# FPGA_Bypass_3V3.net
KiCad netlist of a schematic drawn in Altium Designer
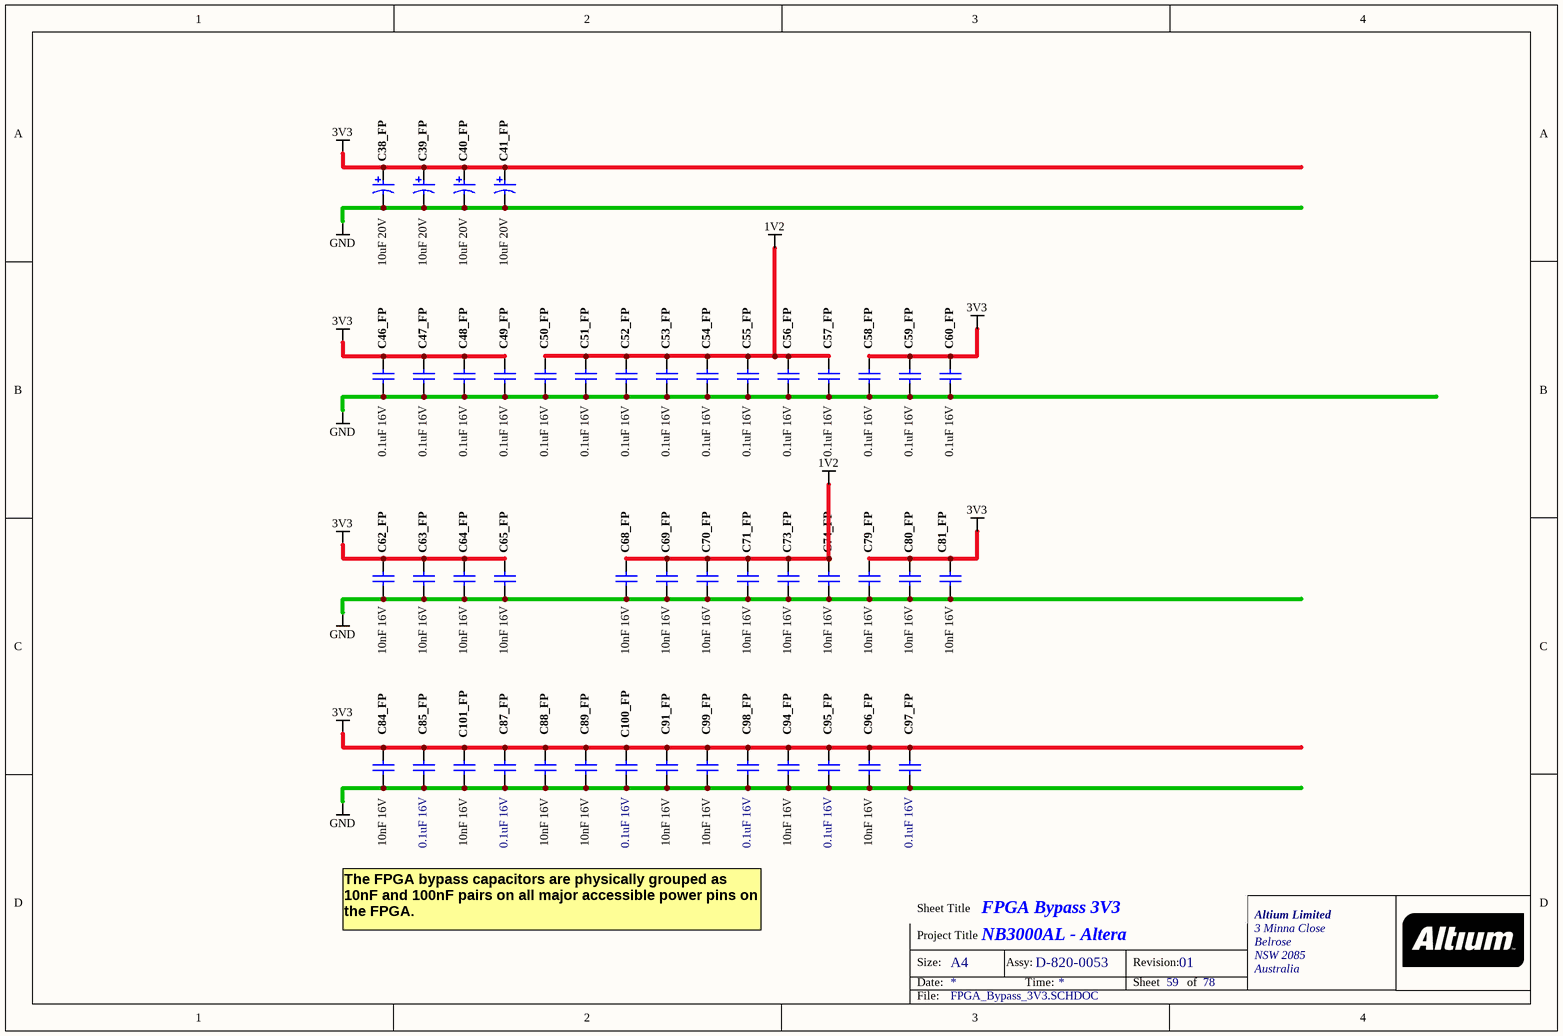
[diagram p0: FPGA_Bypass_3V3.SCHDOC]

(export (version "E")
  (design (tool "Eeschema 10.0.6"))
  (components
    (comp (ref "C38_FP")
      (value "10uF 20V")
      (footprint "CAPC3528-STAR")
      (description "Capacitor, Tantalum, 10uF 10% 20V MCCT-B (3528)")
      (fields (field (name "TOLERANCE") "10 %"))
      (libsource (lib "altium-import") (part "root_0_CAP-P_"))
    )
    (comp (ref "C39_FP")
      (value "10uF 20V")
      (footprint "CAPC3528-STAR")
      (description "Capacitor, Tantalum, 10uF 10% 20V MCCT-B (3528)")
      (fields (field (name "TOLERANCE") "10 %"))
      (libsource (lib "altium-import") (part "root_0_CAP-P_"))
    )
    (comp (ref "C40_FP")
      (value "10uF 20V")
      (footprint "CAPC3528-STAR")
      (description "Capacitor, Tantalum, 10uF 10% 20V MCCT-B (3528)")
      (fields (field (name "TOLERANCE") "10 %"))
      (libsource (lib "altium-import") (part "root_0_CAP-P_"))
    )
    (comp (ref "C41_FP")
      (value "10uF 20V")
      (footprint "CAPC3528-STAR")
      (description "Capacitor, Tantalum, 10uF 10% 20V MCCT-B (3528)")
      (fields (field (name "TOLERANCE") "10 %"))
      (libsource (lib "altium-import") (part "root_0_CAP-P_"))
    )
    (comp (ref "C46_FP")
      (value "0.1uF 16V")
      (footprint "CAPC1005-STAR")
      (description "Capacitor, Ceramic, 0.1uF 10% 16V 0402 (1005) X7R")
      (fields (field (name "TOLERANCE") "10 %"))
      (libsource (lib "altium-import") (part "root_0_mirrored_CAP-NP_"))
    )
    (comp (ref "C47_FP")
      (value "0.1uF 16V")
      (footprint "CAPC1005-STAR")
      (description "Capacitor, Ceramic, 0.1uF 10% 16V 0402 (1005) X7R")
      (fields (field (name "TOLERANCE") "10 %"))
      (libsource (lib "altium-import") (part "root_0_mirrored_CAP-NP_"))
    )
    (comp (ref "C48_FP")
      (value "0.1uF 16V")
      (footprint "CAPC1005-STAR")
      (description "Capacitor, Ceramic, 0.1uF 10% 16V 0402 (1005) X7R")
      (fields (field (name "TOLERANCE") "10 %"))
      (libsource (lib "altium-import") (part "root_0_mirrored_CAP-NP_"))
    )
    (comp (ref "C49_FP")
      (value "0.1uF 16V")
      (footprint "CAPC1005-STAR")
      (description "Capacitor, Ceramic, 0.1uF 10% 16V 0402 (1005) X7R")
      (fields (field (name "TOLERANCE") "10 %"))
      (libsource (lib "altium-import") (part "root_0_mirrored_CAP-NP_"))
    )
    (comp (ref "C50_FP")
      (value "0.1uF 16V")
      (footprint "CAPC1005-STAR")
      (description "Capacitor, Ceramic, 0.1uF 10% 16V 0402 (1005) X7R")
      (fields (field (name "TOLERANCE") "10 %"))
      (libsource (lib "altium-import") (part "root_0_mirrored_CAP-NP_"))
    )
    (comp (ref "C51_FP")
      (value "0.1uF 16V")
      (footprint "CAPC1005-STAR")
      (description "Capacitor, Ceramic, 0.1uF 10% 16V 0402 (1005) X7R")
      (fields (field (name "TOLERANCE") "10 %"))
      (libsource (lib "altium-import") (part "root_0_mirrored_CAP-NP_"))
    )
    (comp (ref "C52_FP")
      (value "0.1uF 16V")
      (footprint "CAPC1005-STAR")
      (description "Capacitor, Ceramic, 0.1uF 10% 16V 0402 (1005) X7R")
      (fields (field (name "TOLERANCE") "10 %"))
      (libsource (lib "altium-import") (part "root_0_mirrored_CAP-NP_"))
    )
    (comp (ref "C53_FP")
      (value "0.1uF 16V")
      (footprint "CAPC1005-STAR")
      (description "Capacitor, Ceramic, 0.1uF 10% 16V 0402 (1005) X7R")
      (fields (field (name "TOLERANCE") "10 %"))
      (libsource (lib "altium-import") (part "root_0_mirrored_CAP-NP_"))
    )
    (comp (ref "C54_FP")
      (value "0.1uF 16V")
      (footprint "CAPC1005-STAR")
      (description "Capacitor, Ceramic, 0.1uF 10% 16V 0402 (1005) X7R")
      (fields (field (name "TOLERANCE") "10 %"))
      (libsource (lib "altium-import") (part "root_0_mirrored_CAP-NP_"))
    )
    (comp (ref "C55_FP")
      (value "0.1uF 16V")
      (footprint "CAPC1005-STAR")
      (description "Capacitor, Ceramic, 0.1uF 10% 16V 0402 (1005) X7R")
      (fields (field (name "TOLERANCE") "10 %"))
      (libsource (lib "altium-import") (part "root_0_mirrored_CAP-NP_"))
    )
    (comp (ref "C56_FP")
      (value "0.1uF 16V")
      (footprint "CAPC1005-STAR")
      (description "Capacitor, Ceramic, 0.1uF 10% 16V 0402 (1005) X7R")
      (fields (field (name "TOLERANCE") "10 %"))
      (libsource (lib "altium-import") (part "root_0_mirrored_CAP-NP_"))
    )
    (comp (ref "C57_FP")
      (value "0.1uF 16V")
      (footprint "CAPC1005-STAR")
      (description "Capacitor, Ceramic, 0.1uF 10% 16V 0402 (1005) X7R")
      (fields (field (name "TOLERANCE") "10 %"))
      (libsource (lib "altium-import") (part "root_0_mirrored_CAP-NP_"))
    )
    (comp (ref "C58_FP")
      (value "0.1uF 16V")
      (footprint "CAPC1005-STAR")
      (description "Capacitor, Ceramic, 0.1uF 10% 16V 0402 (1005) X7R")
      (fields (field (name "TOLERANCE") "10 %"))
      (libsource (lib "altium-import") (part "root_0_mirrored_CAP-NP_"))
    )
    (comp (ref "C59_FP")
      (value "0.1uF 16V")
      (footprint "CAPC1005-STAR")
      (description "Capacitor, Ceramic, 0.1uF 10% 16V 0402 (1005) X7R")
      (fields (field (name "TOLERANCE") "10 %"))
      (libsource (lib "altium-import") (part "root_0_mirrored_CAP-NP_"))
    )
    (comp (ref "C60_FP")
      (value "0.1uF 16V")
      (footprint "CAPC1005-STAR")
      (description "Capacitor, Ceramic, 0.1uF 10% 16V 0402 (1005) X7R")
      (fields (field (name "TOLERANCE") "10 %"))
      (libsource (lib "altium-import") (part "root_0_mirrored_CAP-NP_"))
    )
    (comp (ref "C62_FP")
      (value "10nF 16V")
      (footprint "CAPC1005-STAR")
      (description "Capacitor, Ceramic, 10nF 10% 16V 0402 (1005) X7R")
      (fields (field (name "TOLERANCE") "10 %"))
      (libsource (lib "altium-import") (part "root_0_CAP-NP_"))
    )
    (comp (ref "C63_FP")
      (value "10nF 16V")
      (footprint "CAPC1005-STAR")
      (description "Capacitor, Ceramic, 10nF 10% 16V 0402 (1005) X7R")
      (fields (field (name "TOLERANCE") "10 %"))
      (libsource (lib "altium-import") (part "root_0_CAP-NP_"))
    )
    (comp (ref "C64_FP")
      (value "10nF 16V")
      (footprint "CAPC1005-STAR")
      (description "Capacitor, Ceramic, 10nF 10% 16V 0402 (1005) X7R")
      (fields (field (name "TOLERANCE") "10 %"))
      (libsource (lib "altium-import") (part "root_0_CAP-NP_"))
    )
    (comp (ref "C65_FP")
      (value "10nF 16V")
      (footprint "CAPC1005-STAR")
      (description "Capacitor, Ceramic, 10nF 10% 16V 0402 (1005) X7R")
      (fields (field (name "TOLERANCE") "10 %"))
      (libsource (lib "altium-import") (part "root_0_CAP-NP_"))
    )
    (comp (ref "C68_FP")
      (value "10nF 16V")
      (footprint "CAPC1005-STAR")
      (description "Capacitor, Ceramic, 10nF 10% 16V 0402 (1005) X7R")
      (fields (field (name "TOLERANCE") "10 %"))
      (libsource (lib "altium-import") (part "root_0_CAP-NP_"))
    )
    (comp (ref "C69_FP")
      (value "10nF 16V")
      (footprint "CAPC1005-STAR")
      (description "Capacitor, Ceramic, 10nF 10% 16V 0402 (1005) X7R")
      (fields (field (name "TOLERANCE") "10 %"))
      (libsource (lib "altium-import") (part "root_0_CAP-NP_"))
    )
    (comp (ref "C70_FP")
      (value "10nF 16V")
      (footprint "CAPC1005-STAR")
      (description "Capacitor, Ceramic, 10nF 10% 16V 0402 (1005) X7R")
      (fields (field (name "TOLERANCE") "10 %"))
      (libsource (lib "altium-import") (part "root_0_CAP-NP_"))
    )
    (comp (ref "C71_FP")
      (value "10nF 16V")
      (footprint "CAPC1005-STAR")
      (description "Capacitor, Ceramic, 10nF 10% 16V 0402 (1005) X7R")
      (fields (field (name "TOLERANCE") "10 %"))
      (libsource (lib "altium-import") (part "root_0_CAP-NP_"))
    )
    (comp (ref "C73_FP")
      (value "10nF 16V")
      (footprint "CAPC1005-STAR")
      (description "Capacitor, Ceramic, 10nF 10% 16V 0402 (1005) X7R")
      (fields (field (name "TOLERANCE") "10 %"))
      (libsource (lib "altium-import") (part "root_0_CAP-NP_"))
    )
    (comp (ref "C74_FP")
      (value "10nF 16V")
      (footprint "CAPC1005-STAR")
      (description "Capacitor, Ceramic, 10nF 10% 16V 0402 (1005) X7R")
      (fields (field (name "TOLERANCE") "10 %"))
      (libsource (lib "altium-import") (part "root_0_CAP-NP_"))
    )
    (comp (ref "C79_FP")
      (value "10nF 16V")
      (footprint "CAPC1005-STAR")
      (description "Capacitor, Ceramic, 10nF 10% 16V 0402 (1005) X7R")
      (fields (field (name "TOLERANCE") "10 %"))
      (libsource (lib "altium-import") (part "root_0_CAP-NP_"))
    )
    (comp (ref "C80_FP")
      (value "10nF 16V")
      (footprint "CAPC1005-STAR")
      (description "Capacitor, Ceramic, 10nF 10% 16V 0402 (1005) X7R")
      (fields (field (name "TOLERANCE") "10 %"))
      (libsource (lib "altium-import") (part "root_0_CAP-NP_"))
    )
    (comp (ref "C81_FP")
      (value "10nF 16V")
      (footprint "CAPC1005-STAR")
      (description "Capacitor, Ceramic, 10nF 10% 16V 0402 (1005) X7R")
      (fields (field (name "TOLERANCE") "10 %"))
      (libsource (lib "altium-import") (part "root_0_CAP-NP_"))
    )
    (comp (ref "C84_FP")
      (value "10nF 16V")
      (footprint "CAPC1005-STAR")
      (description "Capacitor, Ceramic, 10nF 10% 16V 0402 (1005) X7R")
      (fields (field (name "TOLERANCE") "10 %"))
      (libsource (lib "altium-import") (part "root_0_CAP-NP_"))
    )
    (comp (ref "C85_FP")
      (value "0.1uF 16V")
      (footprint "CAPC1005-STAR")
      (description "Capacitor, Ceramic, 0.1uF 10% 16V 0402 (1005) X7R")
      (fields (field (name "TOLERANCE") "10%"))
      (libsource (lib "AltiumDesignLibrary") (part "CAP-NP"))
    )
    (comp (ref "C87_FP")
      (value "0.1uF 16V")
      (footprint "CAPC1005-STAR")
      (description "Capacitor, Ceramic, 0.1uF 10% 16V 0402 (1005) X7R")
      (fields (field (name "TOLERANCE") "10%"))
      (libsource (lib "AltiumDesignLibrary") (part "CAP-NP"))
    )
    (comp (ref "C88_FP")
      (value "10nF 16V")
      (footprint "CAPC1005-STAR")
      (description "Capacitor, Ceramic, 10nF 10% 16V 0402 (1005) X7R")
      (fields (field (name "TOLERANCE") "10 %"))
      (libsource (lib "altium-import") (part "root_0_CAP-NP_"))
    )
    (comp (ref "C89_FP")
      (value "10nF 16V")
      (footprint "CAPC1005-STAR")
      (description "Capacitor, Ceramic, 10nF 10% 16V 0402 (1005) X7R")
      (fields (field (name "TOLERANCE") "10 %"))
      (libsource (lib "altium-import") (part "root_0_CAP-NP_"))
    )
    (comp (ref "C91_FP")
      (value "10nF 16V")
      (footprint "CAPC1005-STAR")
      (description "Capacitor, Ceramic, 10nF 10% 16V 0402 (1005) X7R")
      (fields (field (name "TOLERANCE") "10 %"))
      (libsource (lib "altium-import") (part "root_0_CAP-NP_"))
    )
    (comp (ref "C94_FP")
      (value "10nF 16V")
      (footprint "CAPC1005-STAR")
      (description "Capacitor, Ceramic, 10nF 10% 16V 0402 (1005) X7R")
      (fields (field (name "TOLERANCE") "10 %"))
      (libsource (lib "altium-import") (part "root_0_CAP-NP_"))
    )
    (comp (ref "C95_FP")
      (value "0.1uF 16V")
      (footprint "CAPC1005-STAR")
      (description "Capacitor, Ceramic, 0.1uF 10% 16V 0402 (1005) X7R")
      (fields (field (name "TOLERANCE") "10%"))
      (libsource (lib "AltiumDesignLibrary") (part "CAP-NP"))
    )
    (comp (ref "C96_FP")
      (value "10nF 16V")
      (footprint "CAPC1005-STAR")
      (description "Capacitor, Ceramic, 10nF 10% 16V 0402 (1005) X7R")
      (fields (field (name "TOLERANCE") "10 %"))
      (libsource (lib "altium-import") (part "root_0_CAP-NP_"))
    )
    (comp (ref "C97_FP")
      (value "0.1uF 16V")
      (footprint "CAPC1005-STAR")
      (description "Capacitor, Ceramic, 0.1uF 10% 16V 0402 (1005) X7R")
      (fields (field (name "TOLERANCE") "10%"))
      (libsource (lib "AltiumDesignLibrary") (part "CAP-NP"))
    )
    (comp (ref "C98_FP")
      (value "0.1uF 16V")
      (footprint "CAPC1005-STAR")
      (description "Capacitor, Ceramic, 0.1uF 10% 16V 0402 (1005) X7R")
      (fields (field (name "TOLERANCE") "10%"))
      (libsource (lib "AltiumDesignLibrary") (part "CAP-NP"))
    )
    (comp (ref "C99_FP")
      (value "10nF 16V")
      (footprint "CAPC1005-STAR")
      (description "Capacitor, Ceramic, 10nF 10% 16V 0402 (1005) X7R")
      (fields (field (name "TOLERANCE") "10 %"))
      (libsource (lib "altium-import") (part "root_0_CAP-NP_"))
    )
    (comp (ref "C100_FP")
      (value "0.1uF 16V")
      (footprint "CAPC1005-STAR")
      (description "Capacitor, Ceramic, 0.1uF 10% 16V 0402 (1005) X7R")
      (fields (field (name "TOLERANCE") "10%"))
      (libsource (lib "AltiumDesignLibrary") (part "CAP-NP"))
    )
    (comp (ref "C101_FP")
      (value "10nF 16V")
      (footprint "CAPC1005-STAR")
      (description "Capacitor, Ceramic, 10nF 10% 16V 0402 (1005) X7R")
      (fields (field (name "TOLERANCE") "10 %"))
      (libsource (lib "altium-import") (part "root_0_CAP-NP_"))
    )
  )
  (nets
    (net (code "1") (name "1V2") (class "Default")
      (node (ref "C50_FP") (pin "1") (pinfunction "1_1") (pintype "passive"))
      (node (ref "C51_FP") (pin "1") (pinfunction "1_1") (pintype "passive"))
      (node (ref "C52_FP") (pin "1") (pinfunction "1_1") (pintype "passive"))
      (node (ref "C53_FP") (pin "1") (pinfunction "1_1") (pintype "passive"))
      (node (ref "C54_FP") (pin "1") (pinfunction "1_1") (pintype "passive"))
      (node (ref "C55_FP") (pin "1") (pinfunction "1_1") (pintype "passive"))
      (node (ref "C56_FP") (pin "1") (pinfunction "1_1") (pintype "passive"))
      (node (ref "C57_FP") (pin "1") (pinfunction "1_1") (pintype "passive"))
      (node (ref "C68_FP") (pin "1") (pinfunction "1_1") (pintype "passive"))
      (node (ref "C69_FP") (pin "1") (pinfunction "1_1") (pintype "passive"))
      (node (ref "C70_FP") (pin "1") (pinfunction "1_1") (pintype "passive"))
      (node (ref "C71_FP") (pin "1") (pinfunction "1_1") (pintype "passive"))
      (node (ref "C73_FP") (pin "1") (pinfunction "1_1") (pintype "passive"))
      (node (ref "C74_FP") (pin "1") (pinfunction "1_1") (pintype "passive"))
    )
    (net (code "2") (name "3V3") (class "Default")
      (node (ref "C100_FP") (pin "1") (pinfunction "1_1") (pintype "passive"))
      (node (ref "C101_FP") (pin "1") (pinfunction "1_1") (pintype "passive"))
      (node (ref "C38_FP") (pin "1") (pinfunction "1_1") (pintype "passive"))
      (node (ref "C39_FP") (pin "1") (pinfunction "1_1") (pintype "passive"))
      (node (ref "C40_FP") (pin "1") (pinfunction "1_1") (pintype "passive"))
      (node (ref "C41_FP") (pin "1") (pinfunction "1_1") (pintype "passive"))
      (node (ref "C46_FP") (pin "1") (pinfunction "1_1") (pintype "passive"))
      (node (ref "C47_FP") (pin "1") (pinfunction "1_1") (pintype "passive"))
      (node (ref "C48_FP") (pin "1") (pinfunction "1_1") (pintype "passive"))
      (node (ref "C49_FP") (pin "1") (pinfunction "1_1") (pintype "passive"))
      (node (ref "C58_FP") (pin "1") (pinfunction "1_1") (pintype "passive"))
      (node (ref "C59_FP") (pin "1") (pinfunction "1_1") (pintype "passive"))
      (node (ref "C60_FP") (pin "1") (pinfunction "1_1") (pintype "passive"))
      (node (ref "C62_FP") (pin "1") (pinfunction "1_1") (pintype "passive"))
      (node (ref "C63_FP") (pin "1") (pinfunction "1_1") (pintype "passive"))
      (node (ref "C64_FP") (pin "1") (pinfunction "1_1") (pintype "passive"))
      (node (ref "C65_FP") (pin "1") (pinfunction "1_1") (pintype "passive"))
      (node (ref "C79_FP") (pin "1") (pinfunction "1_1") (pintype "passive"))
      (node (ref "C80_FP") (pin "1") (pinfunction "1_1") (pintype "passive"))
      (node (ref "C81_FP") (pin "1") (pinfunction "1_1") (pintype "passive"))
      (node (ref "C84_FP") (pin "1") (pinfunction "1_1") (pintype "passive"))
      (node (ref "C85_FP") (pin "1") (pinfunction "1_1") (pintype "passive"))
      (node (ref "C87_FP") (pin "1") (pinfunction "1_1") (pintype "passive"))
      (node (ref "C88_FP") (pin "1") (pinfunction "1_1") (pintype "passive"))
      (node (ref "C89_FP") (pin "1") (pinfunction "1_1") (pintype "passive"))
      (node (ref "C91_FP") (pin "1") (pinfunction "1_1") (pintype "passive"))
      (node (ref "C94_FP") (pin "1") (pinfunction "1_1") (pintype "passive"))
      (node (ref "C95_FP") (pin "1") (pinfunction "1_1") (pintype "passive"))
      (node (ref "C96_FP") (pin "1") (pinfunction "1_1") (pintype "passive"))
      (node (ref "C97_FP") (pin "1") (pinfunction "1_1") (pintype "passive"))
      (node (ref "C98_FP") (pin "1") (pinfunction "1_1") (pintype "passive"))
      (node (ref "C99_FP") (pin "1") (pinfunction "1_1") (pintype "passive"))
    )
    (net (code "3") (name "GND") (class "Default")
      (node (ref "C100_FP") (pin "2") (pinfunction "2_2") (pintype "passive"))
      (node (ref "C101_FP") (pin "2") (pinfunction "2_2") (pintype "passive"))
      (node (ref "C38_FP") (pin "2") (pinfunction "2_2") (pintype "passive"))
      (node (ref "C39_FP") (pin "2") (pinfunction "2_2") (pintype "passive"))
      (node (ref "C40_FP") (pin "2") (pinfunction "2_2") (pintype "passive"))
      (node (ref "C41_FP") (pin "2") (pinfunction "2_2") (pintype "passive"))
      (node (ref "C46_FP") (pin "2") (pinfunction "2_2") (pintype "passive"))
      (node (ref "C47_FP") (pin "2") (pinfunction "2_2") (pintype "passive"))
      (node (ref "C48_FP") (pin "2") (pinfunction "2_2") (pintype "passive"))
      (node (ref "C49_FP") (pin "2") (pinfunction "2_2") (pintype "passive"))
      (node (ref "C50_FP") (pin "2") (pinfunction "2_2") (pintype "passive"))
      (node (ref "C51_FP") (pin "2") (pinfunction "2_2") (pintype "passive"))
      (node (ref "C52_FP") (pin "2") (pinfunction "2_2") (pintype "passive"))
      (node (ref "C53_FP") (pin "2") (pinfunction "2_2") (pintype "passive"))
      (node (ref "C54_FP") (pin "2") (pinfunction "2_2") (pintype "passive"))
      (node (ref "C55_FP") (pin "2") (pinfunction "2_2") (pintype "passive"))
      (node (ref "C56_FP") (pin "2") (pinfunction "2_2") (pintype "passive"))
      (node (ref "C57_FP") (pin "2") (pinfunction "2_2") (pintype "passive"))
      (node (ref "C58_FP") (pin "2") (pinfunction "2_2") (pintype "passive"))
      (node (ref "C59_FP") (pin "2") (pinfunction "2_2") (pintype "passive"))
      (node (ref "C60_FP") (pin "2") (pinfunction "2_2") (pintype "passive"))
      (node (ref "C62_FP") (pin "2") (pinfunction "2_2") (pintype "passive"))
      (node (ref "C63_FP") (pin "2") (pinfunction "2_2") (pintype "passive"))
      (node (ref "C64_FP") (pin "2") (pinfunction "2_2") (pintype "passive"))
      (node (ref "C65_FP") (pin "2") (pinfunction "2_2") (pintype "passive"))
      (node (ref "C68_FP") (pin "2") (pinfunction "2_2") (pintype "passive"))
      (node (ref "C69_FP") (pin "2") (pinfunction "2_2") (pintype "passive"))
      (node (ref "C70_FP") (pin "2") (pinfunction "2_2") (pintype "passive"))
      (node (ref "C71_FP") (pin "2") (pinfunction "2_2") (pintype "passive"))
      (node (ref "C73_FP") (pin "2") (pinfunction "2_2") (pintype "passive"))
      (node (ref "C74_FP") (pin "2") (pinfunction "2_2") (pintype "passive"))
      (node (ref "C79_FP") (pin "2") (pinfunction "2_2") (pintype "passive"))
      (node (ref "C80_FP") (pin "2") (pinfunction "2_2") (pintype "passive"))
      (node (ref "C81_FP") (pin "2") (pinfunction "2_2") (pintype "passive"))
      (node (ref "C84_FP") (pin "2") (pinfunction "2_2") (pintype "passive"))
      (node (ref "C85_FP") (pin "2") (pinfunction "2_2") (pintype "passive"))
      (node (ref "C87_FP") (pin "2") (pinfunction "2_2") (pintype "passive"))
      (node (ref "C88_FP") (pin "2") (pinfunction "2_2") (pintype "passive"))
      (node (ref "C89_FP") (pin "2") (pinfunction "2_2") (pintype "passive"))
      (node (ref "C91_FP") (pin "2") (pinfunction "2_2") (pintype "passive"))
      (node (ref "C94_FP") (pin "2") (pinfunction "2_2") (pintype "passive"))
      (node (ref "C95_FP") (pin "2") (pinfunction "2_2") (pintype "passive"))
      (node (ref "C96_FP") (pin "2") (pinfunction "2_2") (pintype "passive"))
      (node (ref "C97_FP") (pin "2") (pinfunction "2_2") (pintype "passive"))
      (node (ref "C98_FP") (pin "2") (pinfunction "2_2") (pintype "passive"))
      (node (ref "C99_FP") (pin "2") (pinfunction "2_2") (pintype "passive"))
    )
  )
)
